# GameSch.net
KiCad netlist of a schematic drawn in EAGLE
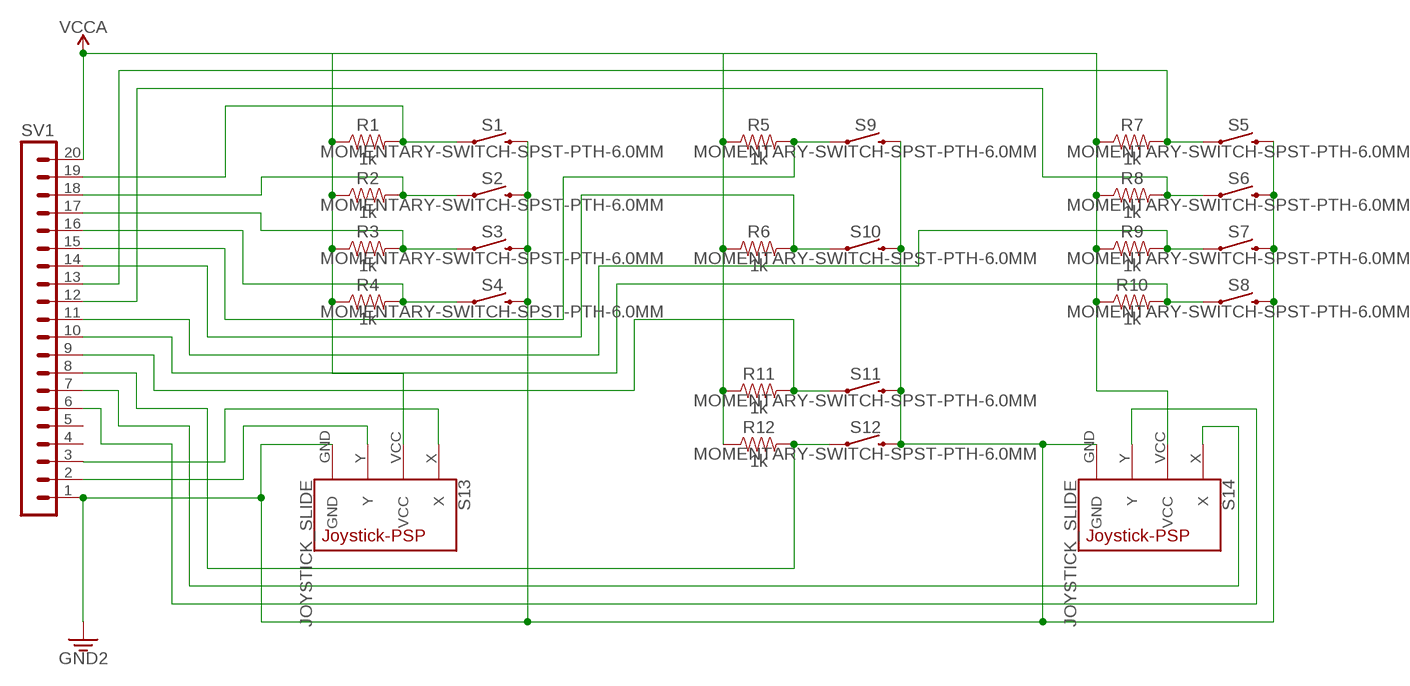
[diagram p0: schematic, sheet 1]

(export (version "E")
  (design (tool "Eeschema 10.0.6"))
  (components
    (comp (ref "R1")
      (value "1k")
      (footprint "eagle-import:AXIAL-0.3")
      (libsource (lib "eagle-import") (part "1KOHM-HORIZ-1/4W-5%"))
    )
    (comp (ref "R2")
      (value "1k")
      (footprint "eagle-import:AXIAL-0.3")
      (libsource (lib "eagle-import") (part "1KOHM-HORIZ-1/4W-5%"))
    )
    (comp (ref "R3")
      (value "1k")
      (footprint "eagle-import:AXIAL-0.3")
      (libsource (lib "eagle-import") (part "1KOHM-HORIZ-1/4W-5%"))
    )
    (comp (ref "R4")
      (value "1k")
      (footprint "eagle-import:AXIAL-0.3")
      (libsource (lib "eagle-import") (part "1KOHM-HORIZ-1/4W-5%"))
    )
    (comp (ref "R5")
      (value "1k")
      (footprint "eagle-import:AXIAL-0.3")
      (libsource (lib "eagle-import") (part "1KOHM-HORIZ-1/4W-5%"))
    )
    (comp (ref "R6")
      (value "1k")
      (footprint "eagle-import:AXIAL-0.3")
      (libsource (lib "eagle-import") (part "1KOHM-HORIZ-1/4W-5%"))
    )
    (comp (ref "R7")
      (value "1k")
      (footprint "eagle-import:AXIAL-0.3")
      (libsource (lib "eagle-import") (part "1KOHM-HORIZ-1/4W-5%"))
    )
    (comp (ref "R8")
      (value "1k")
      (footprint "eagle-import:AXIAL-0.3")
      (libsource (lib "eagle-import") (part "1KOHM-HORIZ-1/4W-5%"))
    )
    (comp (ref "R9")
      (value "1k")
      (footprint "eagle-import:AXIAL-0.3")
      (libsource (lib "eagle-import") (part "1KOHM-HORIZ-1/4W-5%"))
    )
    (comp (ref "R10")
      (value "1k")
      (footprint "eagle-import:AXIAL-0.3")
      (libsource (lib "eagle-import") (part "1KOHM-HORIZ-1/4W-5%"))
    )
    (comp (ref "R11")
      (value "1k")
      (footprint "eagle-import:AXIAL-0.3")
      (libsource (lib "eagle-import") (part "1KOHM-HORIZ-1/4W-5%"))
    )
    (comp (ref "R12")
      (value "1k")
      (footprint "eagle-import:AXIAL-0.3")
      (libsource (lib "eagle-import") (part "1KOHM-HORIZ-1/4W-5%"))
    )
    (comp (ref "S1")
      (value "MOMENTARY-SWITCH-SPST-PTH-6.0MM")
      (footprint "eagle-import:TACTILE_SWITCH_PTH_6.0MM")
      (libsource (lib "eagle-import") (part "MOMENTARY-SWITCH-SPST-PTH-6.0MM"))
    )
    (comp (ref "S2")
      (value "MOMENTARY-SWITCH-SPST-PTH-6.0MM")
      (footprint "eagle-import:TACTILE_SWITCH_PTH_6.0MM")
      (libsource (lib "eagle-import") (part "MOMENTARY-SWITCH-SPST-PTH-6.0MM"))
    )
    (comp (ref "S3")
      (value "MOMENTARY-SWITCH-SPST-PTH-6.0MM")
      (footprint "eagle-import:TACTILE_SWITCH_PTH_6.0MM")
      (libsource (lib "eagle-import") (part "MOMENTARY-SWITCH-SPST-PTH-6.0MM"))
    )
    (comp (ref "S4")
      (value "MOMENTARY-SWITCH-SPST-PTH-6.0MM")
      (footprint "eagle-import:TACTILE_SWITCH_PTH_6.0MM")
      (libsource (lib "eagle-import") (part "MOMENTARY-SWITCH-SPST-PTH-6.0MM"))
    )
    (comp (ref "S5")
      (value "MOMENTARY-SWITCH-SPST-PTH-6.0MM")
      (footprint "eagle-import:TACTILE_SWITCH_PTH_6.0MM")
      (libsource (lib "eagle-import") (part "MOMENTARY-SWITCH-SPST-PTH-6.0MM"))
    )
    (comp (ref "S6")
      (value "MOMENTARY-SWITCH-SPST-PTH-6.0MM")
      (footprint "eagle-import:TACTILE_SWITCH_PTH_6.0MM")
      (libsource (lib "eagle-import") (part "MOMENTARY-SWITCH-SPST-PTH-6.0MM"))
    )
    (comp (ref "S7")
      (value "MOMENTARY-SWITCH-SPST-PTH-6.0MM")
      (footprint "eagle-import:TACTILE_SWITCH_PTH_6.0MM")
      (libsource (lib "eagle-import") (part "MOMENTARY-SWITCH-SPST-PTH-6.0MM"))
    )
    (comp (ref "S8")
      (value "MOMENTARY-SWITCH-SPST-PTH-6.0MM")
      (footprint "eagle-import:TACTILE_SWITCH_PTH_6.0MM")
      (libsource (lib "eagle-import") (part "MOMENTARY-SWITCH-SPST-PTH-6.0MM"))
    )
    (comp (ref "S9")
      (value "MOMENTARY-SWITCH-SPST-PTH-6.0MM")
      (footprint "eagle-import:TACTILE_SWITCH_PTH_6.0MM")
      (libsource (lib "eagle-import") (part "MOMENTARY-SWITCH-SPST-PTH-6.0MM"))
    )
    (comp (ref "S10")
      (value "MOMENTARY-SWITCH-SPST-PTH-6.0MM")
      (footprint "eagle-import:TACTILE_SWITCH_PTH_6.0MM")
      (libsource (lib "eagle-import") (part "MOMENTARY-SWITCH-SPST-PTH-6.0MM"))
    )
    (comp (ref "S11")
      (value "MOMENTARY-SWITCH-SPST-PTH-6.0MM")
      (footprint "eagle-import:TACTILE_SWITCH_PTH_6.0MM")
      (libsource (lib "eagle-import") (part "MOMENTARY-SWITCH-SPST-PTH-6.0MM"))
    )
    (comp (ref "S12")
      (value "MOMENTARY-SWITCH-SPST-PTH-6.0MM")
      (footprint "eagle-import:TACTILE_SWITCH_PTH_6.0MM")
      (libsource (lib "eagle-import") (part "MOMENTARY-SWITCH-SPST-PTH-6.0MM"))
    )
    (comp (ref "S13")
      (value "JOYSTICK_SLIDE")
      (footprint "eagle-import:JOYSTICK-PSP1000")
      (libsource (lib "eagle-import") (part "JOYSTICK_SLIDE"))
    )
    (comp (ref "S14")
      (value "JOYSTICK_SLIDE")
      (footprint "eagle-import:JOYSTICK-PSP1000")
      (libsource (lib "eagle-import") (part "JOYSTICK_SLIDE"))
    )
    (comp (ref "SV1")
      (value "MA20-1")
      (footprint "eagle-import:MA20-1")
      (libsource (lib "eagle-import") (part "MA20-1"))
    )
  )
  (nets
    (net (code "1") (name "GND2") (class "Default")
      (node (ref "S1") (pin "3") (pinfunction "2_3") (pintype "passive"))
      (node (ref "S10") (pin "3") (pinfunction "2_3") (pintype "passive"))
      (node (ref "S11") (pin "3") (pinfunction "2_3") (pintype "passive"))
      (node (ref "S12") (pin "3") (pinfunction "2_3") (pintype "passive"))
      (node (ref "S13") (pin "GND") (pinfunction "GND_GND") (pintype "bidirectional"))
      (node (ref "S14") (pin "GND") (pinfunction "GND_GND") (pintype "bidirectional"))
      (node (ref "S2") (pin "3") (pinfunction "2_3") (pintype "passive"))
      (node (ref "S3") (pin "3") (pinfunction "2_3") (pintype "passive"))
      (node (ref "S4") (pin "3") (pinfunction "2_3") (pintype "passive"))
      (node (ref "S5") (pin "3") (pinfunction "2_3") (pintype "passive"))
      (node (ref "S6") (pin "3") (pinfunction "2_3") (pintype "passive"))
      (node (ref "S7") (pin "3") (pinfunction "2_3") (pintype "passive"))
      (node (ref "S8") (pin "3") (pinfunction "2_3") (pintype "passive"))
      (node (ref "S9") (pin "3") (pinfunction "2_3") (pintype "passive"))
      (node (ref "SV1") (pin "1") (pinfunction "1_1") (pintype "passive"))
    )
    (net (code "2") (name "Net-(R1-2)") (class "Default")
      (node (ref "R1") (pin "P$2") (pinfunction "2_P$2") (pintype "passive"))
      (node (ref "S1") (pin "1") (pinfunction "1_1") (pintype "passive"))
      (node (ref "SV1") (pin "19") (pinfunction "19_19") (pintype "passive"))
    )
    (net (code "3") (name "Net-(R2-2)") (class "Default")
      (node (ref "R2") (pin "P$2") (pinfunction "2_P$2") (pintype "passive"))
      (node (ref "S2") (pin "1") (pinfunction "1_1") (pintype "passive"))
      (node (ref "SV1") (pin "18") (pinfunction "18_18") (pintype "passive"))
    )
    (net (code "4") (name "Net-(R3-2)") (class "Default")
      (node (ref "R3") (pin "P$2") (pinfunction "2_P$2") (pintype "passive"))
      (node (ref "S3") (pin "1") (pinfunction "1_1") (pintype "passive"))
      (node (ref "SV1") (pin "17") (pinfunction "17_17") (pintype "passive"))
    )
    (net (code "5") (name "Net-(R4-2)") (class "Default")
      (node (ref "R4") (pin "P$2") (pinfunction "2_P$2") (pintype "passive"))
      (node (ref "S4") (pin "1") (pinfunction "1_1") (pintype "passive"))
      (node (ref "SV1") (pin "16") (pinfunction "16_16") (pintype "passive"))
    )
    (net (code "6") (name "Net-(R5-2)") (class "Default")
      (node (ref "R5") (pin "P$2") (pinfunction "2_P$2") (pintype "passive"))
      (node (ref "S9") (pin "1") (pinfunction "1_1") (pintype "passive"))
      (node (ref "SV1") (pin "15") (pinfunction "15_15") (pintype "passive"))
    )
    (net (code "7") (name "Net-(R6-2)") (class "Default")
      (node (ref "R6") (pin "P$2") (pinfunction "2_P$2") (pintype "passive"))
      (node (ref "S10") (pin "1") (pinfunction "1_1") (pintype "passive"))
      (node (ref "SV1") (pin "14") (pinfunction "14_14") (pintype "passive"))
    )
    (net (code "8") (name "Net-(R7-2)") (class "Default")
      (node (ref "R7") (pin "P$2") (pinfunction "2_P$2") (pintype "passive"))
      (node (ref "S5") (pin "1") (pinfunction "1_1") (pintype "passive"))
      (node (ref "SV1") (pin "13") (pinfunction "13_13") (pintype "passive"))
    )
    (net (code "9") (name "Net-(R8-2)") (class "Default")
      (node (ref "R8") (pin "P$2") (pinfunction "2_P$2") (pintype "passive"))
      (node (ref "S6") (pin "1") (pinfunction "1_1") (pintype "passive"))
      (node (ref "SV1") (pin "12") (pinfunction "12_12") (pintype "passive"))
    )
    (net (code "10") (name "Net-(R9-2)") (class "Default")
      (node (ref "R9") (pin "P$2") (pinfunction "2_P$2") (pintype "passive"))
      (node (ref "S7") (pin "1") (pinfunction "1_1") (pintype "passive"))
      (node (ref "SV1") (pin "11") (pinfunction "11_11") (pintype "passive"))
    )
    (net (code "11") (name "Net-(R10-2)") (class "Default")
      (node (ref "R10") (pin "P$2") (pinfunction "2_P$2") (pintype "passive"))
      (node (ref "S8") (pin "1") (pinfunction "1_1") (pintype "passive"))
      (node (ref "SV1") (pin "10") (pinfunction "10_10") (pintype "passive"))
    )
    (net (code "12") (name "Net-(R11-2)") (class "Default")
      (node (ref "R11") (pin "P$2") (pinfunction "2_P$2") (pintype "passive"))
      (node (ref "S11") (pin "1") (pinfunction "1_1") (pintype "passive"))
      (node (ref "SV1") (pin "9") (pinfunction "9_9") (pintype "passive"))
    )
    (net (code "13") (name "Net-(R12-2)") (class "Default")
      (node (ref "R12") (pin "P$2") (pinfunction "2_P$2") (pintype "passive"))
      (node (ref "S12") (pin "1") (pinfunction "1_1") (pintype "passive"))
      (node (ref "SV1") (pin "8") (pinfunction "8_8") (pintype "passive"))
    )
    (net (code "14") (name "Net-(S13-PadX)") (class "Default")
      (node (ref "S13") (pin "X") (pinfunction "X_X") (pintype "bidirectional"))
      (node (ref "SV1") (pin "3") (pinfunction "3_3") (pintype "passive"))
    )
    (net (code "15") (name "Net-(S13-PadY)") (class "Default")
      (node (ref "S13") (pin "Y") (pinfunction "Y_Y") (pintype "bidirectional"))
      (node (ref "SV1") (pin "2") (pinfunction "2_2") (pintype "passive"))
    )
    (net (code "16") (name "Net-(S14-PadX)") (class "Default")
      (node (ref "S14") (pin "X") (pinfunction "X_X") (pintype "bidirectional"))
      (node (ref "SV1") (pin "7") (pinfunction "7_7") (pintype "passive"))
    )
    (net (code "17") (name "Net-(S14-PadY)") (class "Default")
      (node (ref "S14") (pin "Y") (pinfunction "Y_Y") (pintype "bidirectional"))
      (node (ref "SV1") (pin "6") (pinfunction "6_6") (pintype "passive"))
    )
    (net (code "18") (name "VCCA") (class "Default")
      (node (ref "R1") (pin "P$1") (pinfunction "1_P$1") (pintype "passive"))
      (node (ref "R10") (pin "P$1") (pinfunction "1_P$1") (pintype "passive"))
      (node (ref "R11") (pin "P$1") (pinfunction "1_P$1") (pintype "passive"))
      (node (ref "R12") (pin "P$1") (pinfunction "1_P$1") (pintype "passive"))
      (node (ref "R2") (pin "P$1") (pinfunction "1_P$1") (pintype "passive"))
      (node (ref "R3") (pin "P$1") (pinfunction "1_P$1") (pintype "passive"))
      (node (ref "R4") (pin "P$1") (pinfunction "1_P$1") (pintype "passive"))
      (node (ref "R5") (pin "P$1") (pinfunction "1_P$1") (pintype "passive"))
      (node (ref "R6") (pin "P$1") (pinfunction "1_P$1") (pintype "passive"))
      (node (ref "R7") (pin "P$1") (pinfunction "1_P$1") (pintype "passive"))
      (node (ref "R8") (pin "P$1") (pinfunction "1_P$1") (pintype "passive"))
      (node (ref "R9") (pin "P$1") (pinfunction "1_P$1") (pintype "passive"))
      (node (ref "S13") (pin "VCC") (pinfunction "VCC_VCC") (pintype "bidirectional"))
      (node (ref "S14") (pin "VCC") (pinfunction "VCC_VCC") (pintype "bidirectional"))
      (node (ref "SV1") (pin "20") (pinfunction "20_20") (pintype "passive"))
    )
    (net (code "19") (name "unconnected-(SV1-Pad4)") (class "Default")
      (node (ref "SV1") (pin "4") (pinfunction "4_4") (pintype "passive"))
    )
    (net (code "20") (name "unconnected-(SV1-Pad5)") (class "Default")
      (node (ref "SV1") (pin "5") (pinfunction "5_5") (pintype "passive"))
    )
  )
)
